# arm_shield_design.net
KiCad netlist of a schematic drawn in EAGLE
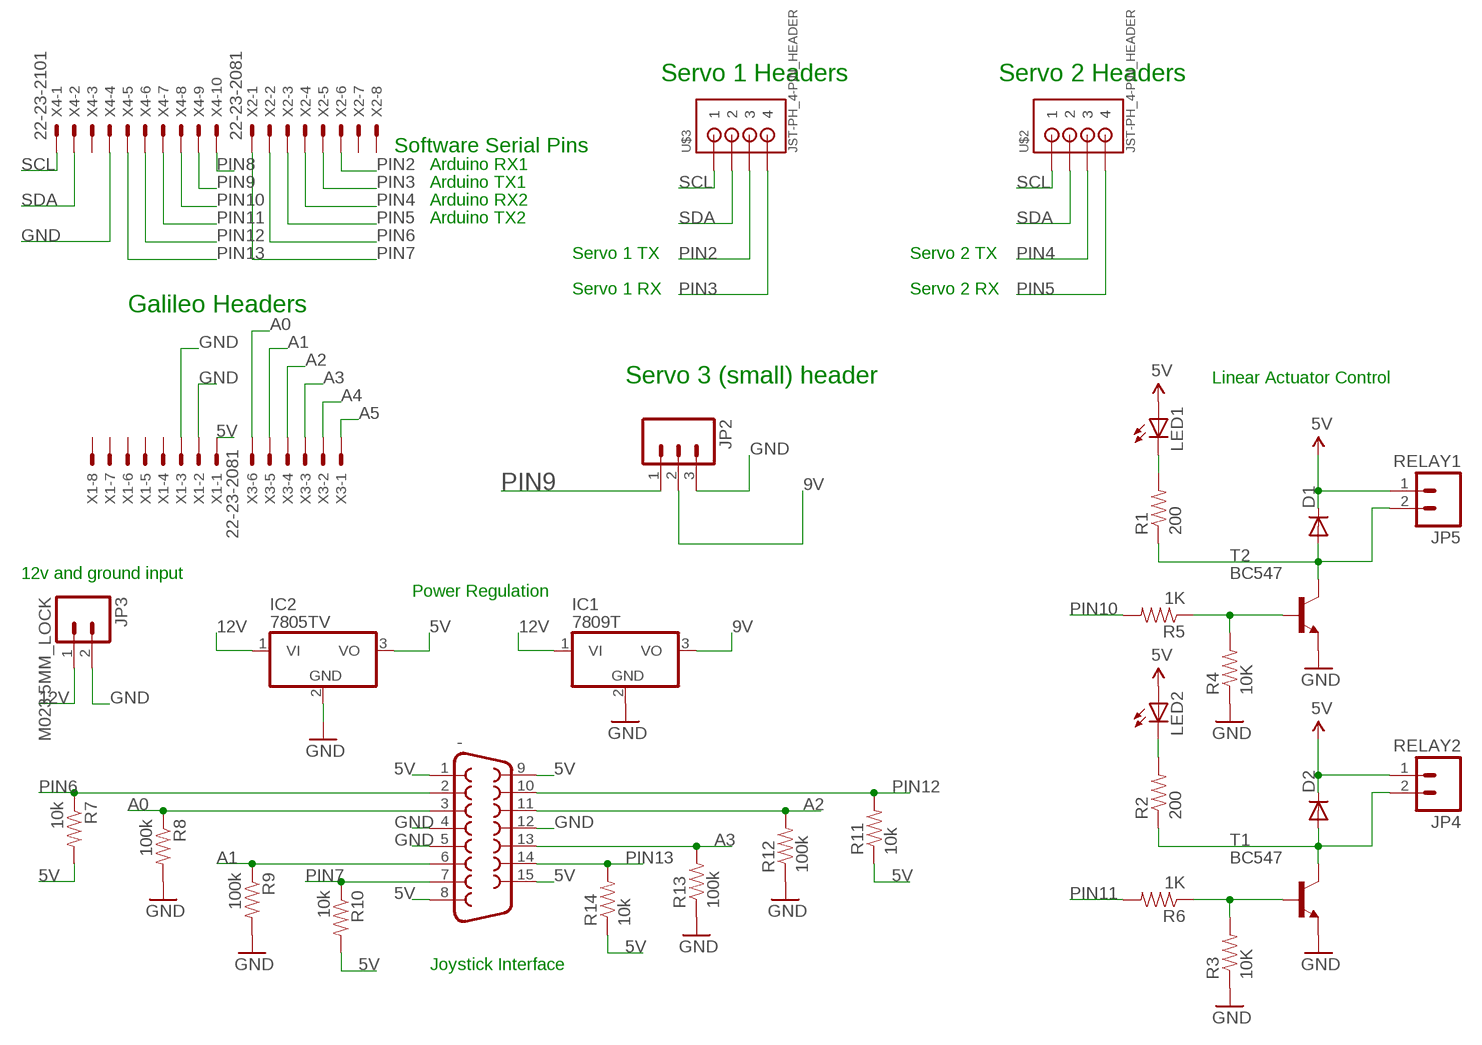
[diagram p0: schematic, sheet 1]

(export (version "E")
  (design (tool "Eeschema 10.0.6"))
  (components
    (comp (ref "-")
      (value "F15HP")
      (footprint "eagle-import:F15HP")
      (libsource (lib "eagle-import") (part "F15HP"))
    )
    (comp (ref "D1")
      (value "DIODE1N4148")
      (footprint "eagle-import:DIODE-1N4148")
      (libsource (lib "eagle-import") (part "DIODE1N4148"))
    )
    (comp (ref "D2")
      (value "DIODE1N4148")
      (footprint "eagle-import:DIODE-1N4148")
      (libsource (lib "eagle-import") (part "DIODE1N4148"))
    )
    (comp (ref "IC1")
      (value "7809T")
      (footprint "eagle-import:TO220V")
      (libsource (lib "eagle-import") (part "78TV05"))
    )
    (comp (ref "IC2")
      (value "7805TV")
      (footprint "eagle-import:TO220V")
      (libsource (lib "eagle-import") (part "78TV05"))
    )
    (comp (ref "JP2")
      (value "M03PTH")
      (footprint "eagle-import:1X03")
      (libsource (lib "eagle-import") (part "M03PTH"))
    )
    (comp (ref "JP3")
      (value "M023.5MM_LOCK")
      (footprint "eagle-import:SCREWTERMINAL-3.5MM-2_LOCK")
      (libsource (lib "eagle-import") (part "M023.5MM_LOCK"))
    )
    (comp (ref "JP4")
      (value "RELAY2")
      (footprint "eagle-import:SCREWTERMINAL-3.5MM-2_LOCK")
      (libsource (lib "eagle-import") (part "M023.5MM_LOCK"))
    )
    (comp (ref "JP5")
      (value "RELAY1")
      (footprint "eagle-import:SCREWTERMINAL-3.5MM-2_LOCK")
      (libsource (lib "eagle-import") (part "M023.5MM_LOCK"))
    )
    (comp (ref "LED1")
      (value "LED3MM")
      (footprint "eagle-import:LED3MM")
      (libsource (lib "eagle-import") (part "LED3MM"))
    )
    (comp (ref "LED2")
      (value "LED3MM")
      (footprint "eagle-import:LED3MM")
      (libsource (lib "eagle-import") (part "LED3MM"))
    )
    (comp (ref "R1")
      (value "200")
      (footprint "eagle-import:AXIAL-0.1")
      (libsource (lib "eagle-import") (part "RESISTORPTH-1/4W-VERT"))
    )
    (comp (ref "R2")
      (value "200")
      (footprint "eagle-import:AXIAL-0.1")
      (libsource (lib "eagle-import") (part "RESISTORPTH-1/4W-VERT"))
    )
    (comp (ref "R3")
      (value "10K")
      (footprint "eagle-import:AXIAL-0.1")
      (libsource (lib "eagle-import") (part "RESISTORPTH-1/4W-VERT"))
    )
    (comp (ref "R4")
      (value "10K")
      (footprint "eagle-import:AXIAL-0.1")
      (libsource (lib "eagle-import") (part "RESISTORPTH-1/4W-VERT"))
    )
    (comp (ref "R5")
      (value "1K")
      (footprint "eagle-import:AXIAL-0.1")
      (libsource (lib "eagle-import") (part "RESISTORPTH-1/4W-VERT"))
    )
    (comp (ref "R6")
      (value "1K")
      (footprint "eagle-import:AXIAL-0.1")
      (libsource (lib "eagle-import") (part "RESISTORPTH-1/4W-VERT"))
    )
    (comp (ref "R7")
      (value "10k")
      (footprint "eagle-import:AXIAL-0.1")
      (libsource (lib "eagle-import") (part "RESISTORPTH-1/4W-VERT"))
    )
    (comp (ref "R8")
      (value "100k")
      (footprint "eagle-import:AXIAL-0.1")
      (libsource (lib "eagle-import") (part "RESISTORPTH-1/4W-VERT"))
    )
    (comp (ref "R9")
      (value "100k")
      (footprint "eagle-import:AXIAL-0.1")
      (libsource (lib "eagle-import") (part "RESISTORPTH-1/4W-VERT"))
    )
    (comp (ref "R10")
      (value "10k")
      (footprint "eagle-import:AXIAL-0.1")
      (libsource (lib "eagle-import") (part "RESISTORPTH-1/4W-VERT"))
    )
    (comp (ref "R11")
      (value "10k")
      (footprint "eagle-import:AXIAL-0.1")
      (libsource (lib "eagle-import") (part "RESISTORPTH-1/4W-VERT"))
    )
    (comp (ref "R12")
      (value "100k")
      (footprint "eagle-import:AXIAL-0.1")
      (libsource (lib "eagle-import") (part "RESISTORPTH-1/4W-VERT"))
    )
    (comp (ref "R13")
      (value "100k")
      (footprint "eagle-import:AXIAL-0.1")
      (libsource (lib "eagle-import") (part "RESISTORPTH-1/4W-VERT"))
    )
    (comp (ref "R14")
      (value "10k")
      (footprint "eagle-import:AXIAL-0.1")
      (libsource (lib "eagle-import") (part "RESISTORPTH-1/4W-VERT"))
    )
    (comp (ref "T1")
      (value "BC547")
      (footprint "eagle-import:TO92")
      (libsource (lib "eagle-import") (part "BC547"))
    )
    (comp (ref "T2")
      (value "BC547")
      (footprint "eagle-import:TO92")
      (libsource (lib "eagle-import") (part "BC547"))
    )
    (comp (ref "U$2")
      (value "JST-PH_4-PIN_HEADER")
      (footprint "eagle-import:JST_B4B-PH_HEADER")
      (fields (field (name "MPN") "S4B-PH-K-S(LF)(SN)"))
      (libsource (lib "eagle-import") (part "JST-PH_4-PIN_HEADER"))
    )
    (comp (ref "U$3")
      (value "JST-PH_4-PIN_HEADER")
      (footprint "eagle-import:JST_B4B-PH_HEADER")
      (fields (field (name "MPN") "S4B-PH-K-S(LF)(SN)"))
      (libsource (lib "eagle-import") (part "JST-PH_4-PIN_HEADER"))
    )
    (comp (ref "X1")
      (value "22-23-2081")
      (footprint "eagle-import:22-23-2081")
      (fields (field (name "MF") "MOLEX"))
      (libsource (lib "eagle-import") (part "22-23-2081"))
    )
    (comp (ref "X2")
      (value "22-23-2081")
      (footprint "eagle-import:22-23-2081")
      (fields (field (name "MF") "MOLEX"))
      (libsource (lib "eagle-import") (part "22-23-2081"))
    )
    (comp (ref "X3")
      (value "22-23-2061")
      (footprint "eagle-import:22-23-2061")
      (fields (field (name "MF") "MOLEX"))
      (libsource (lib "eagle-import") (part "22-23-2061"))
    )
    (comp (ref "X4")
      (value "22-23-2101")
      (footprint "eagle-import:22-23-2101")
      (fields (field (name "MF") "MOLEX"))
      (libsource (lib "eagle-import") (part "22-23-2101"))
    )
  )
  (nets
    (net (code "1") (name "/9V") (class "Default")
      (node (ref "IC1") (pin "3") (pinfunction "VO_3") (pintype "passive"))
      (node (ref "JP2") (pin "2") (pinfunction "2_2") (pintype "passive"))
    )
    (net (code "2") (name "/12V") (class "Default")
      (node (ref "IC1") (pin "1") (pinfunction "VI_1") (pintype "input"))
      (node (ref "IC2") (pin "1") (pinfunction "VI_1") (pintype "input"))
      (node (ref "JP3") (pin "1") (pinfunction "1_1") (pintype "passive"))
    )
    (net (code "3") (name "/A0") (class "Default")
      (node (ref "-") (pin "3") (pinfunction "3_3") (pintype "passive"))
      (node (ref "R8") (pin "P$1") (pinfunction "1_P$1") (pintype "passive"))
      (node (ref "X3") (pin "6") (pinfunction "S_6") (pintype "passive"))
    )
    (net (code "4") (name "/A1") (class "Default")
      (node (ref "-") (pin "6") (pinfunction "6_6") (pintype "passive"))
      (node (ref "R9") (pin "P$1") (pinfunction "1_P$1") (pintype "passive"))
      (node (ref "X3") (pin "5") (pinfunction "S_5") (pintype "passive"))
    )
    (net (code "5") (name "/A2") (class "Default")
      (node (ref "-") (pin "11") (pinfunction "11_11") (pintype "passive"))
      (node (ref "R12") (pin "P$2") (pinfunction "2_P$2") (pintype "passive"))
      (node (ref "X3") (pin "4") (pinfunction "S_4") (pintype "passive"))
    )
    (net (code "6") (name "/A3") (class "Default")
      (node (ref "-") (pin "13") (pinfunction "13_13") (pintype "passive"))
      (node (ref "R13") (pin "P$2") (pinfunction "2_P$2") (pintype "passive"))
      (node (ref "X3") (pin "3") (pinfunction "S_3") (pintype "passive"))
    )
    (net (code "7") (name "/A4") (class "Default")
      (node (ref "X3") (pin "2") (pinfunction "S_2") (pintype "passive"))
    )
    (net (code "8") (name "/A5") (class "Default")
      (node (ref "X3") (pin "1") (pinfunction "S_1") (pintype "passive"))
    )
    (net (code "9") (name "/PIN2") (class "Default")
      (node (ref "U$3") (pin "P3") (pinfunction "3_P3") (pintype "bidirectional"))
      (node (ref "X2") (pin "6") (pinfunction "S_6") (pintype "passive"))
    )
    (net (code "10") (name "/PIN3") (class "Default")
      (node (ref "U$3") (pin "P4") (pinfunction "4_P4") (pintype "bidirectional"))
      (node (ref "X2") (pin "5") (pinfunction "S_5") (pintype "passive"))
    )
    (net (code "11") (name "/PIN4") (class "Default")
      (node (ref "U$2") (pin "P3") (pinfunction "3_P3") (pintype "bidirectional"))
      (node (ref "X2") (pin "4") (pinfunction "S_4") (pintype "passive"))
    )
    (net (code "12") (name "/PIN5") (class "Default")
      (node (ref "U$2") (pin "P4") (pinfunction "4_P4") (pintype "bidirectional"))
      (node (ref "X2") (pin "3") (pinfunction "S_3") (pintype "passive"))
    )
    (net (code "13") (name "/PIN6") (class "Default")
      (node (ref "-") (pin "2") (pinfunction "2_2") (pintype "passive"))
      (node (ref "R7") (pin "P$1") (pinfunction "1_P$1") (pintype "passive"))
      (node (ref "X2") (pin "2") (pinfunction "S_2") (pintype "passive"))
    )
    (net (code "14") (name "/PIN7") (class "Default")
      (node (ref "-") (pin "7") (pinfunction "7_7") (pintype "passive"))
      (node (ref "R10") (pin "P$1") (pinfunction "1_P$1") (pintype "passive"))
      (node (ref "X2") (pin "1") (pinfunction "S_1") (pintype "passive"))
    )
    (net (code "15") (name "/PIN8") (class "Default")
      (node (ref "X4") (pin "10") (pinfunction "S_10") (pintype "passive"))
    )
    (net (code "16") (name "/PIN9") (class "Default")
      (node (ref "JP2") (pin "1") (pinfunction "1_1") (pintype "passive"))
      (node (ref "X4") (pin "9") (pinfunction "S_9") (pintype "passive"))
    )
    (net (code "17") (name "/PIN10") (class "Default")
      (node (ref "R5") (pin "P$2") (pinfunction "2_P$2") (pintype "passive"))
      (node (ref "X4") (pin "8") (pinfunction "S_8") (pintype "passive"))
    )
    (net (code "18") (name "/PIN11") (class "Default")
      (node (ref "R6") (pin "P$2") (pinfunction "2_P$2") (pintype "passive"))
      (node (ref "X4") (pin "7") (pinfunction "S_7") (pintype "passive"))
    )
    (net (code "19") (name "/PIN12") (class "Default")
      (node (ref "-") (pin "10") (pinfunction "10_10") (pintype "passive"))
      (node (ref "R11") (pin "P$2") (pinfunction "2_P$2") (pintype "passive"))
      (node (ref "X4") (pin "6") (pinfunction "S_6") (pintype "passive"))
    )
    (net (code "20") (name "/PIN13") (class "Default")
      (node (ref "-") (pin "14") (pinfunction "14_14") (pintype "passive"))
      (node (ref "R14") (pin "P$2") (pinfunction "2_P$2") (pintype "passive"))
      (node (ref "X4") (pin "5") (pinfunction "S_5") (pintype "passive"))
    )
    (net (code "21") (name "/SCL") (class "Default")
      (node (ref "U$2") (pin "P1") (pinfunction "1_P1") (pintype "bidirectional"))
      (node (ref "U$3") (pin "P1") (pinfunction "1_P1") (pintype "bidirectional"))
      (node (ref "X4") (pin "1") (pinfunction "S_1") (pintype "passive"))
    )
    (net (code "22") (name "/SDA") (class "Default")
      (node (ref "U$2") (pin "P2") (pinfunction "2_P2") (pintype "bidirectional"))
      (node (ref "U$3") (pin "P2") (pinfunction "2_P2") (pintype "bidirectional"))
      (node (ref "X4") (pin "2") (pinfunction "S_2") (pintype "passive"))
    )
    (net (code "23") (name "5V") (class "Default")
      (node (ref "-") (pin "1") (pinfunction "1_1") (pintype "passive"))
      (node (ref "-") (pin "15") (pinfunction "15_15") (pintype "passive"))
      (node (ref "-") (pin "8") (pinfunction "8_8") (pintype "passive"))
      (node (ref "-") (pin "9") (pinfunction "9_9") (pintype "passive"))
      (node (ref "D1") (pin "C") (pinfunction "C_C") (pintype "passive"))
      (node (ref "D2") (pin "C") (pinfunction "C_C") (pintype "passive"))
      (node (ref "IC2") (pin "3") (pinfunction "VO_3") (pintype "passive"))
      (node (ref "JP4") (pin "1") (pinfunction "1_1") (pintype "passive"))
      (node (ref "JP5") (pin "1") (pinfunction "1_1") (pintype "passive"))
      (node (ref "LED1") (pin "A") (pinfunction "A_A") (pintype "passive"))
      (node (ref "LED2") (pin "A") (pinfunction "A_A") (pintype "passive"))
      (node (ref "R10") (pin "P$2") (pinfunction "2_P$2") (pintype "passive"))
      (node (ref "R11") (pin "P$1") (pinfunction "1_P$1") (pintype "passive"))
      (node (ref "R14") (pin "P$1") (pinfunction "1_P$1") (pintype "passive"))
      (node (ref "R7") (pin "P$2") (pinfunction "2_P$2") (pintype "passive"))
      (node (ref "X1") (pin "1") (pinfunction "S_1") (pintype "passive"))
    )
    (net (code "24") (name "GND") (class "Default")
      (node (ref "-") (pin "12") (pinfunction "12_12") (pintype "passive"))
      (node (ref "-") (pin "4") (pinfunction "4_4") (pintype "passive"))
      (node (ref "-") (pin "5") (pinfunction "5_5") (pintype "passive"))
      (node (ref "IC1") (pin "2") (pinfunction "GND_2") (pintype "passive"))
      (node (ref "IC2") (pin "2") (pinfunction "GND_2") (pintype "passive"))
      (node (ref "JP2") (pin "3") (pinfunction "3_3") (pintype "passive"))
      (node (ref "JP3") (pin "2") (pinfunction "2_2") (pintype "passive"))
      (node (ref "R12") (pin "P$1") (pinfunction "1_P$1") (pintype "passive"))
      (node (ref "R13") (pin "P$1") (pinfunction "1_P$1") (pintype "passive"))
      (node (ref "R3") (pin "P$1") (pinfunction "1_P$1") (pintype "passive"))
      (node (ref "R4") (pin "P$1") (pinfunction "1_P$1") (pintype "passive"))
      (node (ref "R8") (pin "P$2") (pinfunction "2_P$2") (pintype "passive"))
      (node (ref "R9") (pin "P$2") (pinfunction "2_P$2") (pintype "passive"))
      (node (ref "T1") (pin "1") (pinfunction "E_1") (pintype "passive"))
      (node (ref "T2") (pin "1") (pinfunction "E_1") (pintype "passive"))
      (node (ref "X1") (pin "2") (pinfunction "S_2") (pintype "passive"))
      (node (ref "X1") (pin "3") (pinfunction "S_3") (pintype "passive"))
      (node (ref "X4") (pin "4") (pinfunction "S_4") (pintype "passive"))
    )
    (net (code "25") (name "Net-(LED1-C)") (class "Default")
      (node (ref "LED1") (pin "K") (pinfunction "C_K") (pintype "passive"))
      (node (ref "R1") (pin "P$2") (pinfunction "2_P$2") (pintype "passive"))
    )
    (net (code "26") (name "Net-(LED2-C)") (class "Default")
      (node (ref "LED2") (pin "K") (pinfunction "C_K") (pintype "passive"))
      (node (ref "R2") (pin "P$2") (pinfunction "2_P$2") (pintype "passive"))
    )
    (net (code "27") (name "Net-(R1-1)") (class "Default")
      (node (ref "D1") (pin "A") (pinfunction "A_A") (pintype "passive"))
      (node (ref "JP5") (pin "2") (pinfunction "2_2") (pintype "passive"))
      (node (ref "R1") (pin "P$1") (pinfunction "1_P$1") (pintype "passive"))
      (node (ref "T2") (pin "3") (pinfunction "C_3") (pintype "passive"))
    )
    (net (code "28") (name "Net-(R2-1)") (class "Default")
      (node (ref "D2") (pin "A") (pinfunction "A_A") (pintype "passive"))
      (node (ref "JP4") (pin "2") (pinfunction "2_2") (pintype "passive"))
      (node (ref "R2") (pin "P$1") (pinfunction "1_P$1") (pintype "passive"))
      (node (ref "T1") (pin "3") (pinfunction "C_3") (pintype "passive"))
    )
    (net (code "29") (name "Net-(R3-2)") (class "Default")
      (node (ref "R3") (pin "P$2") (pinfunction "2_P$2") (pintype "passive"))
      (node (ref "R6") (pin "P$1") (pinfunction "1_P$1") (pintype "passive"))
      (node (ref "T1") (pin "2") (pinfunction "B_2") (pintype "passive"))
    )
    (net (code "30") (name "Net-(R4-2)") (class "Default")
      (node (ref "R4") (pin "P$2") (pinfunction "2_P$2") (pintype "passive"))
      (node (ref "R5") (pin "P$1") (pinfunction "1_P$1") (pintype "passive"))
      (node (ref "T2") (pin "2") (pinfunction "B_2") (pintype "passive"))
    )
    (net (code "31") (name "unconnected-(X1D-S-Pad4)") (class "Default")
      (node (ref "X1") (pin "4") (pinfunction "S_4") (pintype "passive"))
    )
    (net (code "32") (name "unconnected-(X1E-S-Pad5)") (class "Default")
      (node (ref "X1") (pin "5") (pinfunction "S_5") (pintype "passive"))
    )
    (net (code "33") (name "unconnected-(X1F-S-Pad6)") (class "Default")
      (node (ref "X1") (pin "6") (pinfunction "S_6") (pintype "passive"))
    )
    (net (code "34") (name "unconnected-(X1G-S-Pad7)") (class "Default")
      (node (ref "X1") (pin "7") (pinfunction "S_7") (pintype "passive"))
    )
    (net (code "35") (name "unconnected-(X1H-S-Pad8)") (class "Default")
      (node (ref "X1") (pin "8") (pinfunction "S_8") (pintype "passive"))
    )
    (net (code "36") (name "unconnected-(X2G-S-Pad7)") (class "Default")
      (node (ref "X2") (pin "7") (pinfunction "S_7") (pintype "passive"))
    )
    (net (code "37") (name "unconnected-(X2H-S-Pad8)") (class "Default")
      (node (ref "X2") (pin "8") (pinfunction "S_8") (pintype "passive"))
    )
    (net (code "38") (name "unconnected-(X4D-S-Pad3)") (class "Default")
      (node (ref "X4") (pin "3") (pinfunction "S_3") (pintype "passive"))
    )
  )
)
